# ArduinoNano.net
KiCad netlist of a schematic drawn in EAGLE
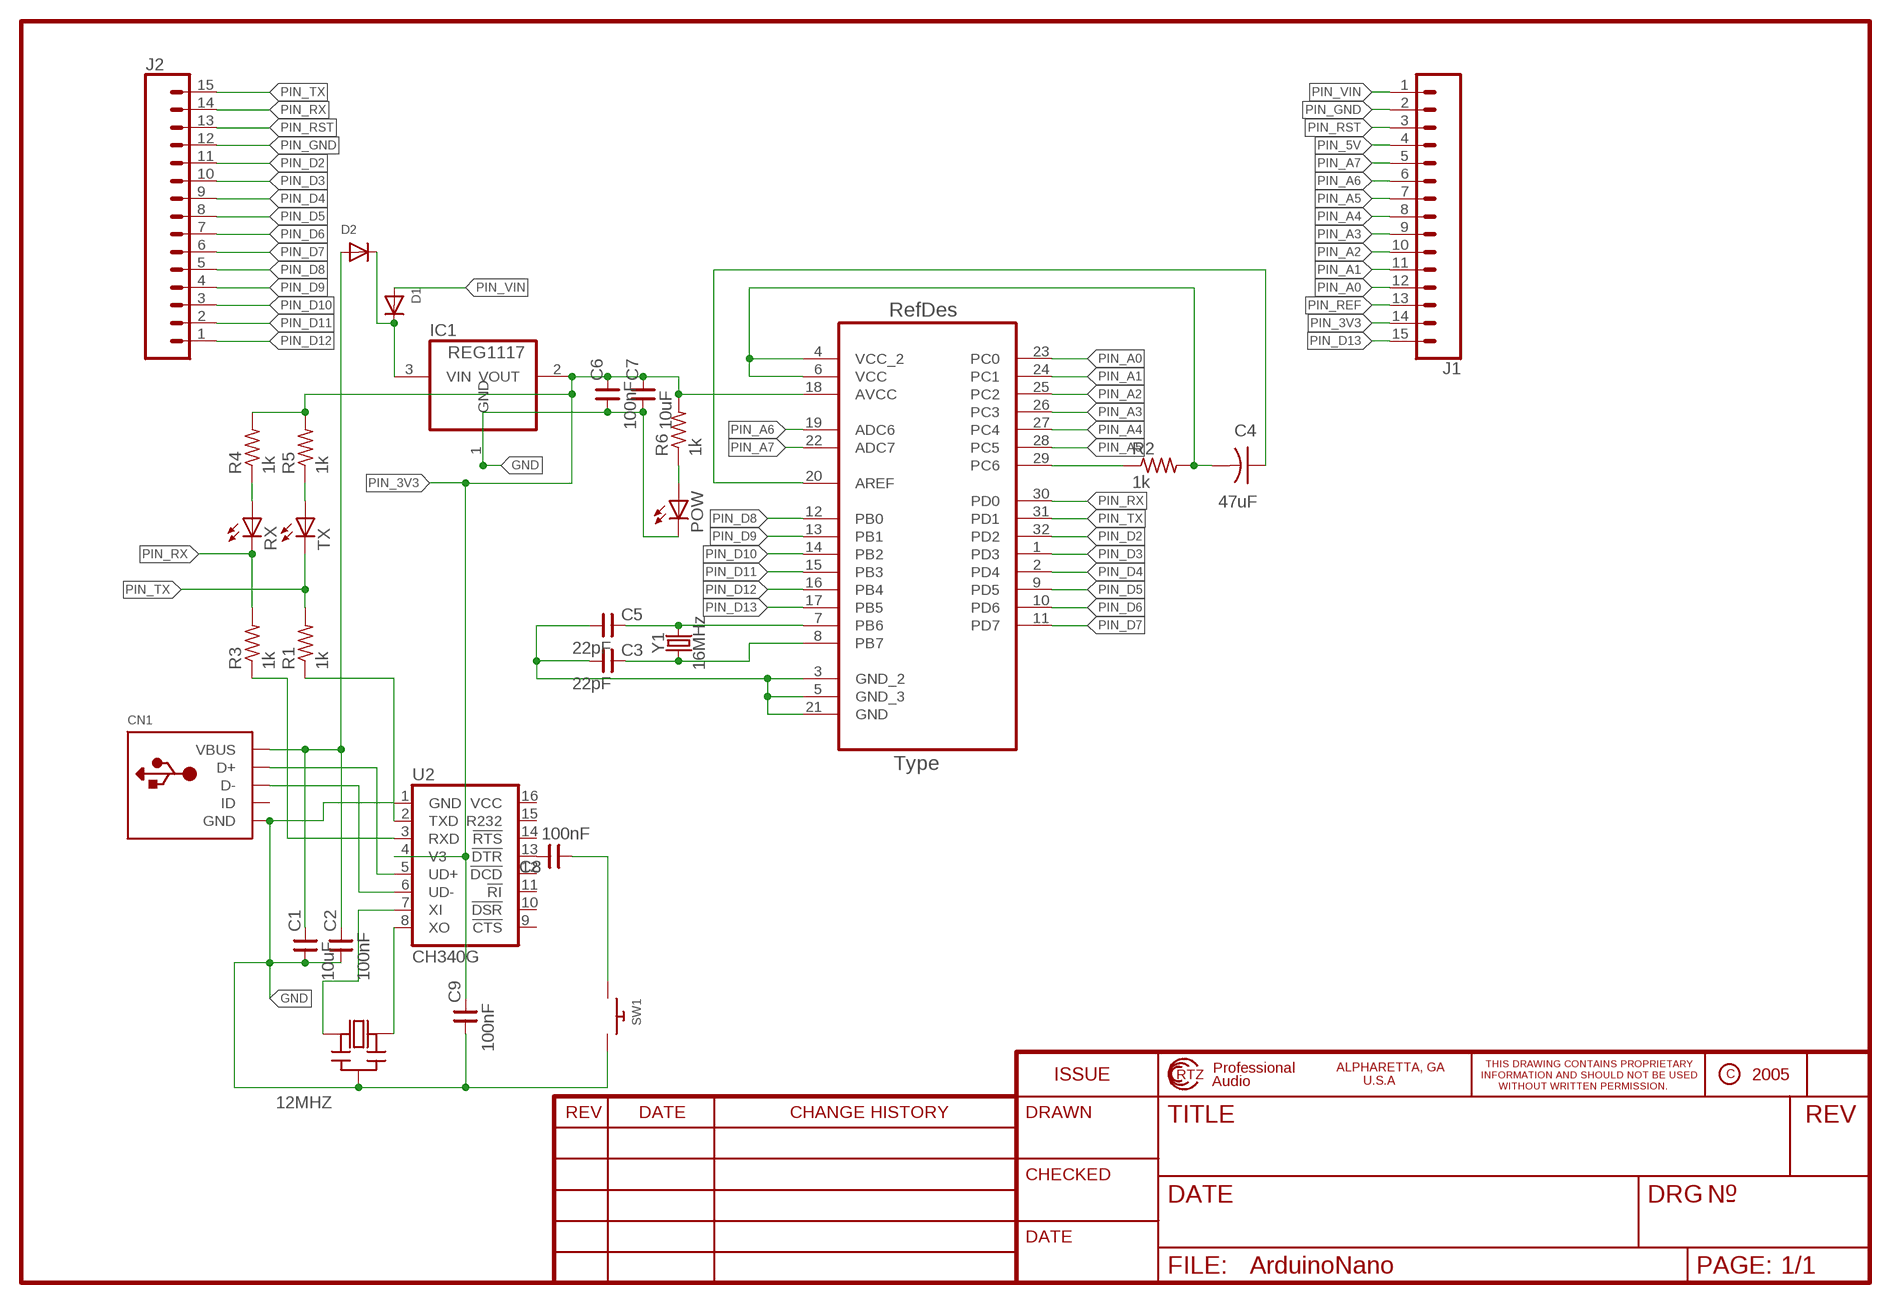
[diagram p0: schematic, sheet 1]

(export (version "E")
  (design (tool "Eeschema 10.0.6"))
  (components
    (comp (ref "12MHZ")
      (value "CERMOSCILL-THM")
      (footprint "eagle-import:CERM_OSC")
      (libsource (lib "eagle-import") (part "CERMOSCILL-THM"))
    )
    (comp (ref "C1")
      (value "10uF")
      (footprint "eagle-import:0603")
      (libsource (lib "eagle-import") (part "CNP-0603"))
    )
    (comp (ref "C2")
      (value "100nF")
      (footprint "eagle-import:0603")
      (libsource (lib "eagle-import") (part "CNP-0603"))
    )
    (comp (ref "C3")
      (value "22pF")
      (footprint "eagle-import:0603")
      (libsource (lib "eagle-import") (part "CNP-0603"))
    )
    (comp (ref "C4")
      (value "47uF")
      (footprint "eagle-import:C1210")
      (libsource (lib "eagle-import") (part "C-USC1210"))
    )
    (comp (ref "C5")
      (value "22pF")
      (footprint "eagle-import:0603")
      (libsource (lib "eagle-import") (part "CNP-0603"))
    )
    (comp (ref "C6")
      (value "100nF")
      (footprint "eagle-import:0603")
      (libsource (lib "eagle-import") (part "CNP-0603"))
    )
    (comp (ref "C7")
      (value "10uF")
      (footprint "eagle-import:0603")
      (libsource (lib "eagle-import") (part "CNP-0603"))
    )
    (comp (ref "C8")
      (value "100nF")
      (footprint "eagle-import:0603")
      (libsource (lib "eagle-import") (part "CNP-0603"))
    )
    (comp (ref "C9")
      (value "100nF")
      (footprint "eagle-import:0603")
      (libsource (lib "eagle-import") (part "CNP-0603"))
    )
    (comp (ref "CN1")
      (value "USBMINIB")
      (footprint "eagle-import:USB-MINIB")
      (libsource (lib "eagle-import") (part "USBMINIB"))
    )
    (comp (ref "D1")
      (value "DIODESOD-323F")
      (footprint "eagle-import:SOD-323F")
      (libsource (lib "eagle-import") (part "adafruit_420_DIODESOD-323F"))
    )
    (comp (ref "D2")
      (value "DIODESOD-323F")
      (footprint "eagle-import:SOD-323F")
      (libsource (lib "eagle-import") (part "DIODESOD-323F"))
    )
    (comp (ref "IC1")
      (value "REG1117")
      (footprint "eagle-import:SOT223")
      (libsource (lib "eagle-import") (part "REG1117"))
    )
    (comp (ref "J1")
      (value "CONN_15")
      (footprint "eagle-import:1X15")
      (libsource (lib "eagle-import") (part "CONN_15"))
    )
    (comp (ref "J2")
      (value "CONN_15")
      (footprint "eagle-import:1X15")
      (libsource (lib "eagle-import") (part "CONN_15"))
    )
    (comp (ref "POW")
      (value "LEDCHIP-LED0603")
      (footprint "eagle-import:CHIP-LED0603")
      (libsource (lib "eagle-import") (part "LEDCHIP-LED0603"))
    )
    (comp (ref "R1")
      (value "1k")
      (footprint "eagle-import:R0603")
      (libsource (lib "eagle-import") (part "R-US_R0603"))
    )
    (comp (ref "R2")
      (value "1k")
      (footprint "eagle-import:R0603")
      (libsource (lib "eagle-import") (part "R-US_R0603"))
    )
    (comp (ref "R3")
      (value "1k")
      (footprint "eagle-import:R0603")
      (libsource (lib "eagle-import") (part "R-US_R0603"))
    )
    (comp (ref "R4")
      (value "1k")
      (footprint "eagle-import:R0603")
      (libsource (lib "eagle-import") (part "R-US_R0603"))
    )
    (comp (ref "R5")
      (value "1k")
      (footprint "eagle-import:R0603")
      (libsource (lib "eagle-import") (part "R-US_R0603"))
    )
    (comp (ref "R6")
      (value "1k")
      (footprint "eagle-import:R0603")
      (libsource (lib "eagle-import") (part "R-US_R0603"))
    )
    (comp (ref "RX")
      (value "LEDCHIPLED_0603")
      (footprint "eagle-import:CHIPLED_0603")
      (libsource (lib "eagle-import") (part "adafruit_420_LEDCHIPLED_0603"))
    )
    (comp (ref "SW1")
      (value "SWITCH_PUSHBUTTONEVQ-PE")
      (footprint "eagle-import:TACT_PANA-EVQ")
      (libsource (lib "eagle-import") (part "SWITCH_PUSHBUTTONEVQ-PE"))
    )
    (comp (ref "TX")
      (value "LEDCHIPLED_0603")
      (footprint "eagle-import:CHIPLED_0603")
      (libsource (lib "eagle-import") (part "adafruit_420_LEDCHIPLED_0603"))
    )
    (comp (ref "U1")
      (value "ATMEGA328P-AU")
      (footprint "eagle-import:QFP80P900X900X120-32N")
      (libsource (lib "eagle-import") (part "ATMEGA328P-AU"))
    )
    (comp (ref "U2")
      (value "CH340G")
      (footprint "eagle-import:SO016")
      (libsource (lib "eagle-import") (part "CH340GSMD"))
    )
    (comp (ref "Y1")
      (value "16MHz")
      (footprint "eagle-import:HC49US")
      (libsource (lib "eagle-import") (part "CRYSTAL-16MHZPTH-HC49US"))
    )
  )
  (nets
    (net (code "1") (name "GND") (class "Default")
      (node (ref "12MHZ") (pin "P$2") (pinfunction "GND_P$2") (pintype "bidirectional"))
      (node (ref "C1") (pin "1") (pinfunction "1_1") (pintype "passive"))
      (node (ref "C2") (pin "1") (pinfunction "1_1") (pintype "passive"))
      (node (ref "C6") (pin "1") (pinfunction "1_1") (pintype "passive"))
      (node (ref "C7") (pin "1") (pinfunction "1_1") (pintype "passive"))
      (node (ref "C9") (pin "1") (pinfunction "1_1") (pintype "passive"))
      (node (ref "CN1") (pin "GND") (pinfunction "GND_GND") (pintype "power_in"))
      (node (ref "IC1") (pin "1") (pinfunction "GND_1") (pintype "power_in"))
      (node (ref "POW") (pin "C") (pinfunction "C_C") (pintype "passive"))
      (node (ref "SW1") (pin "P$2") (pinfunction "P$2_P$2") (pintype "passive"))
      (node (ref "U2") (pin "1") (pinfunction "GND_1") (pintype "bidirectional"))
    )
    (net (code "2") (name "Net-(12MHZ-IN)") (class "Default")
      (node (ref "12MHZ") (pin "P$1") (pinfunction "IN_P$1") (pintype "bidirectional"))
      (node (ref "U2") (pin "7") (pinfunction "XI_7") (pintype "bidirectional"))
    )
    (net (code "3") (name "Net-(12MHZ-OUT)") (class "Default")
      (node (ref "12MHZ") (pin "P$3") (pinfunction "OUT_P$3") (pintype "bidirectional"))
      (node (ref "U2") (pin "8") (pinfunction "XO_8") (pintype "bidirectional"))
    )
    (net (code "4") (name "Net-(C1-Pad2)") (class "Default")
      (node (ref "C1") (pin "2") (pinfunction "2_2") (pintype "passive"))
      (node (ref "C2") (pin "2") (pinfunction "2_2") (pintype "passive"))
      (node (ref "CN1") (pin "VBUS") (pinfunction "VBUS_VBUS") (pintype "power_in"))
      (node (ref "D2") (pin "A") (pinfunction "A_A") (pintype "passive"))
    )
    (net (code "5") (name "Net-(C8-Pad1)") (class "Default")
      (node (ref "C8") (pin "1") (pinfunction "1_1") (pintype "passive"))
      (node (ref "SW1") (pin "P$1") (pinfunction "P$1_P$1") (pintype "passive"))
    )
    (net (code "6") (name "Net-(IC1-VIN)") (class "Default")
      (node (ref "D1") (pin "C") (pinfunction "C_C") (pintype "passive"))
      (node (ref "D2") (pin "C") (pinfunction "C_C") (pintype "passive"))
      (node (ref "IC1") (pin "3") (pinfunction "VIN_3") (pintype "input"))
    )
    (net (code "7") (name "Net-(POW-PadA)") (class "Default")
      (node (ref "POW") (pin "A") (pinfunction "A_A") (pintype "passive"))
      (node (ref "R6") (pin "1") (pinfunction "1_1") (pintype "passive"))
    )
    (net (code "8") (name "Net-(R4-Pad1)") (class "Default")
      (node (ref "R4") (pin "1") (pinfunction "1_1") (pintype "passive"))
      (node (ref "RX") (pin "A") (pinfunction "A_A") (pintype "passive"))
    )
    (net (code "9") (name "Net-(R5-Pad1)") (class "Default")
      (node (ref "R5") (pin "1") (pinfunction "1_1") (pintype "passive"))
      (node (ref "TX") (pin "A") (pinfunction "A_A") (pintype "passive"))
    )
    (net (code "10") (name "Net-(U1-AREF)") (class "Default")
      (node (ref "C4") (pin "1") (pinfunction "1_1") (pintype "passive"))
      (node (ref "U1") (pin "20") (pinfunction "AREF_20") (pintype "input"))
    )
    (net (code "11") (name "Net-(U1-GND)") (class "Default")
      (node (ref "C3") (pin "1") (pinfunction "1_1") (pintype "passive"))
      (node (ref "C5") (pin "1") (pinfunction "1_1") (pintype "passive"))
      (node (ref "U1") (pin "21") (pinfunction "GND_21") (pintype "passive"))
      (node (ref "U1") (pin "3") (pinfunction "GND_2_3") (pintype "passive"))
      (node (ref "U1") (pin "5") (pinfunction "GND_3_5") (pintype "passive"))
    )
    (net (code "12") (name "Net-(U1-PB6)") (class "Default")
      (node (ref "C5") (pin "2") (pinfunction "2_2") (pintype "passive"))
      (node (ref "U1") (pin "7") (pinfunction "PB6_7") (pintype "bidirectional"))
      (node (ref "Y1") (pin "2") (pinfunction "2_2") (pintype "passive"))
    )
    (net (code "13") (name "Net-(U1-PB7)") (class "Default")
      (node (ref "C3") (pin "2") (pinfunction "2_2") (pintype "passive"))
      (node (ref "U1") (pin "8") (pinfunction "PB7_8") (pintype "bidirectional"))
      (node (ref "Y1") (pin "1") (pinfunction "1_1") (pintype "passive"))
    )
    (net (code "14") (name "Net-(U1-PC6)") (class "Default")
      (node (ref "R2") (pin "1") (pinfunction "1_1") (pintype "passive"))
      (node (ref "U1") (pin "29") (pinfunction "PC6_29") (pintype "bidirectional"))
    )
    (net (code "15") (name "Net-(U1-VCC)") (class "Default")
      (node (ref "C4") (pin "2") (pinfunction "2_2") (pintype "passive"))
      (node (ref "R2") (pin "2") (pinfunction "2_2") (pintype "passive"))
      (node (ref "U1") (pin "4") (pinfunction "VCC_2_4") (pintype "power_in"))
      (node (ref "U1") (pin "6") (pinfunction "VCC_6") (pintype "power_in"))
    )
    (net (code "16") (name "Net-(U2-RXD)") (class "Default")
      (node (ref "R3") (pin "1") (pinfunction "1_1") (pintype "passive"))
      (node (ref "U2") (pin "3") (pinfunction "RXD_3") (pintype "bidirectional"))
    )
    (net (code "17") (name "Net-(U2-TXD)") (class "Default")
      (node (ref "R1") (pin "1") (pinfunction "1_1") (pintype "passive"))
      (node (ref "U2") (pin "2") (pinfunction "TXD_2") (pintype "bidirectional"))
    )
    (net (code "18") (name "Net-(U2-UD+)") (class "Default")
      (node (ref "CN1") (pin "D+") (pinfunction "D+_D+") (pintype "bidirectional"))
      (node (ref "U2") (pin "5") (pinfunction "UD+_5") (pintype "bidirectional"))
    )
    (net (code "19") (name "Net-(U2-UD-)") (class "Default")
      (node (ref "CN1") (pin "D-") (pinfunction "D-_D-") (pintype "bidirectional"))
      (node (ref "U2") (pin "6") (pinfunction "UD-_6") (pintype "bidirectional"))
    )
    (net (code "20") (name "Net-(U2-~{DTR})") (class "Default")
      (node (ref "C8") (pin "2") (pinfunction "2_2") (pintype "passive"))
      (node (ref "U2") (pin "13") (pinfunction "~{DTR}_13") (pintype "bidirectional"))
    )
    (net (code "21") (name "PIN_3V3") (class "Default")
      (node (ref "C6") (pin "2") (pinfunction "2_2") (pintype "passive"))
      (node (ref "C7") (pin "2") (pinfunction "2_2") (pintype "passive"))
      (node (ref "C9") (pin "2") (pinfunction "2_2") (pintype "passive"))
      (node (ref "IC1") (pin "2") (pinfunction "VOUT_2") (pintype "output"))
      (node (ref "J1") (pin "14") (pinfunction "14_14") (pintype "passive"))
      (node (ref "R4") (pin "2") (pinfunction "2_2") (pintype "passive"))
      (node (ref "R5") (pin "2") (pinfunction "2_2") (pintype "passive"))
      (node (ref "R6") (pin "2") (pinfunction "2_2") (pintype "passive"))
      (node (ref "U1") (pin "18") (pinfunction "AVCC_18") (pintype "power_in"))
      (node (ref "U2") (pin "4") (pinfunction "V3_4") (pintype "bidirectional"))
    )
    (net (code "22") (name "PIN_5V") (class "Default")
      (node (ref "J1") (pin "4") (pinfunction "4_4") (pintype "passive"))
    )
    (net (code "23") (name "PIN_A0") (class "Default")
      (node (ref "J1") (pin "12") (pinfunction "12_12") (pintype "passive"))
      (node (ref "U1") (pin "23") (pinfunction "PC0_23") (pintype "bidirectional"))
    )
    (net (code "24") (name "PIN_A1") (class "Default")
      (node (ref "J1") (pin "11") (pinfunction "11_11") (pintype "passive"))
      (node (ref "U1") (pin "24") (pinfunction "PC1_24") (pintype "bidirectional"))
    )
    (net (code "25") (name "PIN_A2") (class "Default")
      (node (ref "J1") (pin "10") (pinfunction "10_10") (pintype "passive"))
      (node (ref "U1") (pin "25") (pinfunction "PC2_25") (pintype "bidirectional"))
    )
    (net (code "26") (name "PIN_A3") (class "Default")
      (node (ref "J1") (pin "9") (pinfunction "9_9") (pintype "passive"))
      (node (ref "U1") (pin "26") (pinfunction "PC3_26") (pintype "bidirectional"))
    )
    (net (code "27") (name "PIN_A4") (class "Default")
      (node (ref "J1") (pin "8") (pinfunction "8_8") (pintype "passive"))
      (node (ref "U1") (pin "27") (pinfunction "PC4_27") (pintype "bidirectional"))
    )
    (net (code "28") (name "PIN_A5") (class "Default")
      (node (ref "J1") (pin "7") (pinfunction "7_7") (pintype "passive"))
      (node (ref "U1") (pin "28") (pinfunction "PC5_28") (pintype "bidirectional"))
    )
    (net (code "29") (name "PIN_A6") (class "Default")
      (node (ref "J1") (pin "6") (pinfunction "6_6") (pintype "passive"))
      (node (ref "U1") (pin "19") (pinfunction "ADC6_19") (pintype "input"))
    )
    (net (code "30") (name "PIN_A7") (class "Default")
      (node (ref "J1") (pin "5") (pinfunction "5_5") (pintype "passive"))
      (node (ref "U1") (pin "22") (pinfunction "ADC7_22") (pintype "input"))
    )
    (net (code "31") (name "PIN_D2") (class "Default")
      (node (ref "J2") (pin "11") (pinfunction "11_11") (pintype "passive"))
      (node (ref "U1") (pin "32") (pinfunction "PD2_32") (pintype "bidirectional"))
    )
    (net (code "32") (name "PIN_D3") (class "Default")
      (node (ref "J2") (pin "10") (pinfunction "10_10") (pintype "passive"))
      (node (ref "U1") (pin "1") (pinfunction "PD3_1") (pintype "bidirectional"))
    )
    (net (code "33") (name "PIN_D4") (class "Default")
      (node (ref "J2") (pin "9") (pinfunction "9_9") (pintype "passive"))
      (node (ref "U1") (pin "2") (pinfunction "PD4_2") (pintype "bidirectional"))
    )
    (net (code "34") (name "PIN_D5") (class "Default")
      (node (ref "J2") (pin "8") (pinfunction "8_8") (pintype "passive"))
      (node (ref "U1") (pin "9") (pinfunction "PD5_9") (pintype "bidirectional"))
    )
    (net (code "35") (name "PIN_D6") (class "Default")
      (node (ref "J2") (pin "7") (pinfunction "7_7") (pintype "passive"))
      (node (ref "U1") (pin "10") (pinfunction "PD6_10") (pintype "bidirectional"))
    )
    (net (code "36") (name "PIN_D7") (class "Default")
      (node (ref "J2") (pin "6") (pinfunction "6_6") (pintype "passive"))
      (node (ref "U1") (pin "11") (pinfunction "PD7_11") (pintype "bidirectional"))
    )
    (net (code "37") (name "PIN_D8") (class "Default")
      (node (ref "J2") (pin "5") (pinfunction "5_5") (pintype "passive"))
      (node (ref "U1") (pin "12") (pinfunction "PB0_12") (pintype "bidirectional"))
    )
    (net (code "38") (name "PIN_D9") (class "Default")
      (node (ref "J2") (pin "4") (pinfunction "4_4") (pintype "passive"))
      (node (ref "U1") (pin "13") (pinfunction "PB1_13") (pintype "bidirectional"))
    )
    (net (code "39") (name "PIN_D10") (class "Default")
      (node (ref "J2") (pin "3") (pinfunction "3_3") (pintype "passive"))
      (node (ref "U1") (pin "14") (pinfunction "PB2_14") (pintype "bidirectional"))
    )
    (net (code "40") (name "PIN_D11") (class "Default")
      (node (ref "J2") (pin "2") (pinfunction "2_2") (pintype "passive"))
      (node (ref "U1") (pin "15") (pinfunction "PB3_15") (pintype "bidirectional"))
    )
    (net (code "41") (name "PIN_D12") (class "Default")
      (node (ref "J2") (pin "1") (pinfunction "1_1") (pintype "passive"))
      (node (ref "U1") (pin "16") (pinfunction "PB4_16") (pintype "bidirectional"))
    )
    (net (code "42") (name "PIN_D13") (class "Default")
      (node (ref "J1") (pin "15") (pinfunction "15_15") (pintype "passive"))
      (node (ref "U1") (pin "17") (pinfunction "PB5_17") (pintype "bidirectional"))
    )
    (net (code "43") (name "PIN_GND") (class "Default")
      (node (ref "J1") (pin "2") (pinfunction "2_2") (pintype "passive"))
      (node (ref "J2") (pin "12") (pinfunction "12_12") (pintype "passive"))
    )
    (net (code "44") (name "PIN_REF") (class "Default")
      (node (ref "J1") (pin "13") (pinfunction "13_13") (pintype "passive"))
    )
    (net (code "45") (name "PIN_RST") (class "Default")
      (node (ref "J1") (pin "3") (pinfunction "3_3") (pintype "passive"))
      (node (ref "J2") (pin "13") (pinfunction "13_13") (pintype "passive"))
    )
    (net (code "46") (name "PIN_RX") (class "Default")
      (node (ref "J2") (pin "14") (pinfunction "14_14") (pintype "passive"))
      (node (ref "R3") (pin "2") (pinfunction "2_2") (pintype "passive"))
      (node (ref "RX") (pin "C") (pinfunction "C_C") (pintype "passive"))
      (node (ref "U1") (pin "30") (pinfunction "PD0_30") (pintype "bidirectional"))
    )
    (net (code "47") (name "PIN_TX") (class "Default")
      (node (ref "J2") (pin "15") (pinfunction "15_15") (pintype "passive"))
      (node (ref "R1") (pin "2") (pinfunction "2_2") (pintype "passive"))
      (node (ref "TX") (pin "C") (pinfunction "C_C") (pintype "passive"))
      (node (ref "U1") (pin "31") (pinfunction "PD1_31") (pintype "bidirectional"))
    )
    (net (code "48") (name "PIN_VIN") (class "Default")
      (node (ref "D1") (pin "A") (pinfunction "A_A") (pintype "passive"))
      (node (ref "J1") (pin "1") (pinfunction "1_1") (pintype "passive"))
    )
    (net (code "49") (name "unconnected-(CN1-PadID)") (class "Default")
      (node (ref "CN1") (pin "ID") (pinfunction "ID_ID") (pintype "bidirectional"))
    )
    (net (code "50") (name "unconnected-(U2-R232-Pad15)") (class "Default")
      (node (ref "U2") (pin "15") (pinfunction "R232_15") (pintype "bidirectional"))
    )
    (net (code "51") (name "unconnected-(U2-VCC-Pad16)") (class "Default")
      (node (ref "U2") (pin "16") (pinfunction "VCC_16") (pintype "bidirectional"))
    )
    (net (code "52") (name "unconnected-(U2-~{CTS}-Pad9)") (class "Default")
      (node (ref "U2") (pin "9") (pinfunction "~{CTS}_9") (pintype "bidirectional"))
    )
    (net (code "53") (name "unconnected-(U2-~{DCD}-Pad12)") (class "Default")
      (node (ref "U2") (pin "12") (pinfunction "~{DCD}_12") (pintype "bidirectional"))
    )
    (net (code "54") (name "unconnected-(U2-~{DSR}-Pad10)") (class "Default")
      (node (ref "U2") (pin "10") (pinfunction "~{DSR}_10") (pintype "bidirectional"))
    )
    (net (code "55") (name "unconnected-(U2-~{RI}-Pad11)") (class "Default")
      (node (ref "U2") (pin "11") (pinfunction "~{RI}_11") (pintype "bidirectional"))
    )
    (net (code "56") (name "unconnected-(U2-~{RTS}-Pad14)") (class "Default")
      (node (ref "U2") (pin "14") (pinfunction "~{RTS}_14") (pintype "bidirectional"))
    )
  )
)
